# PCB_Schema.net
KiCad netlist of a schematic drawn in Altium Designer
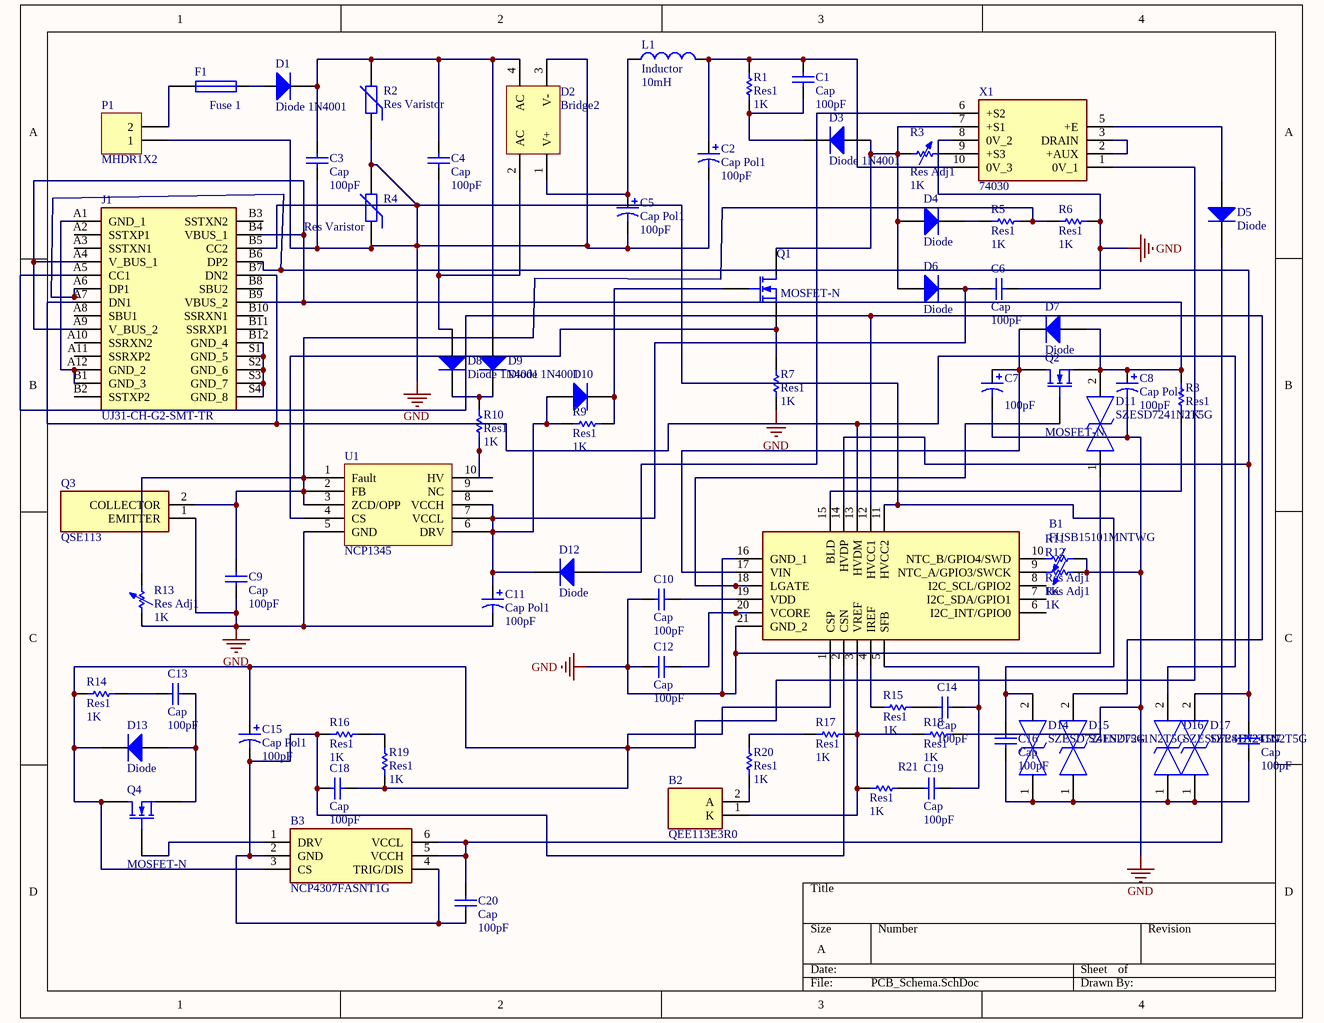
[diagram p0: PCB_Schema.SchDoc]

(export (version "E")
  (design (tool "Eeschema 10.0.6"))
  (components
    (comp (ref "B1")
      (value "FUSB15101MNTWG")
      (footprint "QFN50P400X400X100-21N")
      (description "Programmable USB Type-C and Power Delivery 3.1 Source Controller with PPS Support")
      (fields (field (name "MOUSER PART NUMBER") "863-FUSB15101MNTWG"))
      (libsource (lib "FUSB15101MNTWG") (part "FUSB15101MNTWG"))
    )
    (comp (ref "B2")
      (value "QEE113E3R0")
      (footprint "QEE113E3R0")
      (description "Infrared Emitters infrared Lt Emitting Plastic")
      (fields (field (name "MOUSER PART NUMBER") "512-QEE113E3R0"))
      (libsource (lib "QEE113E3R0") (part "QEE113E3R0"))
    )
    (comp (ref "B3")
      (value "NCP4307FASNT1G")
      (footprint "SOT95P275X110-6N")
      (description "Secondary Side Synchronous Rectification Driver with Dual Supply")
      (libsource (lib "NCP4307FASNT1G") (part "NCP4307FASNT1G"))
    )
    (comp (ref "C1")
      (value "Cap")
      (footprint "RAD-0.3")
      (description "Capacitor")
      (fields (field (name "ALTIUM_VALUE") "100pF") (field (name "PUBLISHER") "Altium Limited"))
      (libsource (lib "Miscellaneous Devices") (part "Cap"))
    )
    (comp (ref "C2")
      (value "Cap Pol1")
      (footprint "RB7.6-15")
      (description "Polarized Capacitor (Radial)")
      (fields (field (name "ALTIUM_VALUE") "100pF") (field (name "PUBLISHER") "Altium Limited"))
      (libsource (lib "Miscellaneous Devices") (part "Cap Pol1"))
    )
    (comp (ref "C3")
      (value "Cap")
      (footprint "RAD-0.3")
      (description "Capacitor")
      (fields (field (name "ALTIUM_VALUE") "100pF") (field (name "PUBLISHER") "Altium Limited"))
      (libsource (lib "Miscellaneous Devices") (part "Cap"))
    )
    (comp (ref "C4")
      (value "Cap")
      (footprint "RAD-0.3")
      (description "Capacitor")
      (fields (field (name "ALTIUM_VALUE") "100pF") (field (name "PUBLISHER") "Altium Limited"))
      (libsource (lib "Miscellaneous Devices") (part "Cap"))
    )
    (comp (ref "C5")
      (value "Cap Pol1")
      (footprint "RB7.6-15")
      (description "Polarized Capacitor (Radial)")
      (fields (field (name "ALTIUM_VALUE") "100pF") (field (name "PUBLISHER") "Altium Limited"))
      (libsource (lib "Miscellaneous Devices") (part "Cap Pol1"))
    )
    (comp (ref "C6")
      (value "Cap")
      (footprint "RAD-0.3")
      (description "Capacitor")
      (fields (field (name "ALTIUM_VALUE") "100pF") (field (name "PUBLISHER") "Altium Limited"))
      (libsource (lib "Miscellaneous Devices") (part "Cap"))
    )
    (comp (ref "C7")
      (value "100pF")
      (footprint "RB7.6-15")
      (description "Polarized Capacitor (Radial)")
      (fields (field (name "PUBLISHER") "Altium Limited"))
      (libsource (lib "Miscellaneous Devices") (part "Cap Pol1"))
    )
    (comp (ref "C8")
      (value "Cap Pol1")
      (footprint "RB7.6-15")
      (description "Polarized Capacitor (Radial)")
      (fields (field (name "ALTIUM_VALUE") "100pF") (field (name "PUBLISHER") "Altium Limited"))
      (libsource (lib "Miscellaneous Devices") (part "Cap Pol1"))
    )
    (comp (ref "C9")
      (value "Cap")
      (footprint "RAD-0.3")
      (description "Capacitor")
      (fields (field (name "ALTIUM_VALUE") "100pF") (field (name "PUBLISHER") "Altium Limited"))
      (libsource (lib "Miscellaneous Devices") (part "Cap"))
    )
    (comp (ref "C10")
      (value "Cap")
      (footprint "RAD-0.3")
      (description "Capacitor")
      (fields (field (name "ALTIUM_VALUE") "100pF") (field (name "PUBLISHER") "Altium Limited"))
      (libsource (lib "Miscellaneous Devices") (part "Cap"))
    )
    (comp (ref "C11")
      (value "Cap Pol1")
      (footprint "RB7.6-15")
      (description "Polarized Capacitor (Radial)")
      (fields (field (name "ALTIUM_VALUE") "100pF") (field (name "PUBLISHER") "Altium Limited"))
      (libsource (lib "Miscellaneous Devices") (part "Cap Pol1"))
    )
    (comp (ref "C12")
      (value "Cap")
      (footprint "RAD-0.3")
      (description "Capacitor")
      (fields (field (name "ALTIUM_VALUE") "100pF") (field (name "PUBLISHER") "Altium Limited"))
      (libsource (lib "Miscellaneous Devices") (part "Cap"))
    )
    (comp (ref "C13")
      (value "Cap")
      (footprint "RAD-0.3")
      (description "Capacitor")
      (fields (field (name "ALTIUM_VALUE") "100pF") (field (name "PUBLISHER") "Altium Limited"))
      (libsource (lib "Miscellaneous Devices") (part "Cap"))
    )
    (comp (ref "C14")
      (value "Cap")
      (footprint "RAD-0.3")
      (description "Capacitor")
      (fields (field (name "ALTIUM_VALUE") "100pF") (field (name "PUBLISHER") "Altium Limited"))
      (libsource (lib "Miscellaneous Devices") (part "Cap"))
    )
    (comp (ref "C15")
      (value "Cap Pol1")
      (footprint "RB7.6-15")
      (description "Polarized Capacitor (Radial)")
      (fields (field (name "ALTIUM_VALUE") "100pF") (field (name "PUBLISHER") "Altium Limited"))
      (libsource (lib "Miscellaneous Devices") (part "Cap Pol1"))
    )
    (comp (ref "C16")
      (value "Cap")
      (footprint "RAD-0.3")
      (description "Capacitor")
      (fields (field (name "ALTIUM_VALUE") "100pF") (field (name "PUBLISHER") "Altium Limited"))
      (libsource (lib "Miscellaneous Devices") (part "Cap"))
    )
    (comp (ref "C17")
      (value "Cap")
      (footprint "RAD-0.3")
      (description "Capacitor")
      (fields (field (name "ALTIUM_VALUE") "100pF") (field (name "PUBLISHER") "Altium Limited"))
      (libsource (lib "Miscellaneous Devices") (part "Cap"))
    )
    (comp (ref "C18")
      (value "Cap")
      (footprint "RAD-0.3")
      (description "Capacitor")
      (fields (field (name "ALTIUM_VALUE") "100pF") (field (name "PUBLISHER") "Altium Limited"))
      (libsource (lib "Miscellaneous Devices") (part "Cap"))
    )
    (comp (ref "C19")
      (value "Cap")
      (footprint "RAD-0.3")
      (description "Capacitor")
      (fields (field (name "ALTIUM_VALUE") "100pF") (field (name "PUBLISHER") "Altium Limited"))
      (libsource (lib "Miscellaneous Devices") (part "Cap"))
    )
    (comp (ref "C20")
      (value "Cap")
      (footprint "RAD-0.3")
      (description "Capacitor")
      (fields (field (name "ALTIUM_VALUE") "100pF") (field (name "PUBLISHER") "Altium Limited"))
      (libsource (lib "Miscellaneous Devices") (part "Cap"))
    )
    (comp (ref "D1")
      (value "Diode 1N4001")
      (footprint "DO-41")
      (description "1 Amp General Purpose Rectifier")
      (fields (field (name "PUBLISHER") "Altium Limited"))
      (libsource (lib "Miscellaneous Devices") (part "Diode 1N4001"))
    )
    (comp (ref "D2")
      (value "Bridge2")
      (footprint "D-46_6A")
      (description "Diode Bridge")
      (fields (field (name "PUBLISHER") "Altium Limited"))
      (libsource (lib "Miscellaneous Devices") (part "Bridge2"))
    )
    (comp (ref "D3")
      (value "Diode 1N4001")
      (footprint "DO-41")
      (description "1 Amp General Purpose Rectifier")
      (fields (field (name "PUBLISHER") "Altium Limited"))
      (libsource (lib "Miscellaneous Devices") (part "Diode 1N4001"))
    )
    (comp (ref "D4")
      (value "Diode")
      (footprint "SMC")
      (description "Default Diode")
      (fields (field (name "PUBLISHER") "Altium Limited"))
      (libsource (lib "Miscellaneous Devices") (part "Diode"))
    )
    (comp (ref "D5")
      (value "Diode")
      (footprint "SMC")
      (description "Default Diode")
      (fields (field (name "PUBLISHER") "Altium Limited"))
      (libsource (lib "Miscellaneous Devices") (part "Diode"))
    )
    (comp (ref "D6")
      (value "Diode")
      (footprint "SMC")
      (description "Default Diode")
      (fields (field (name "PUBLISHER") "Altium Limited"))
      (libsource (lib "Miscellaneous Devices") (part "Diode"))
    )
    (comp (ref "D7")
      (value "Diode")
      (footprint "SMC")
      (description "Default Diode")
      (fields (field (name "PUBLISHER") "Altium Limited"))
      (libsource (lib "Miscellaneous Devices") (part "Diode"))
    )
    (comp (ref "D8")
      (value "Diode 1N4001")
      (footprint "DO-41")
      (description "1 Amp General Purpose Rectifier")
      (fields (field (name "PUBLISHER") "Altium Limited"))
      (libsource (lib "Miscellaneous Devices") (part "Diode 1N4001"))
    )
    (comp (ref "D9")
      (value "Diode 1N4001")
      (footprint "DO-41")
      (description "1 Amp General Purpose Rectifier")
      (fields (field (name "PUBLISHER") "Altium Limited"))
      (libsource (lib "Miscellaneous Devices") (part "Diode 1N4001"))
    )
    (comp (ref "D10")
      (value "~")
      (footprint "SMC")
      (description "Default Diode")
      (fields (field (name "PUBLISHER") "Altium Limited"))
      (libsource (lib "Miscellaneous Devices") (part "Diode"))
    )
    (comp (ref "D11")
      (value "SZESD7241N2T5G")
      (footprint "SZESD7462N2T5G")
      (description "ESD Suppressors / TVS Diodes SZ 24V VRWM ESD PROTECTION")
      (fields (field (name "MOUSER PART NUMBER") "863-SZESD7241N2T5G"))
      (libsource (lib "SZESD7241N2T5G") (part "SZESD7241N2T5G"))
    )
    (comp (ref "D12")
      (value "Diode")
      (footprint "SMC")
      (description "Default Diode")
      (fields (field (name "PUBLISHER") "Altium Limited"))
      (libsource (lib "Miscellaneous Devices") (part "Diode"))
    )
    (comp (ref "D13")
      (value "Diode")
      (footprint "SMC")
      (description "Default Diode")
      (fields (field (name "PUBLISHER") "Altium Limited"))
      (libsource (lib "Miscellaneous Devices") (part "Diode"))
    )
    (comp (ref "D14")
      (value "SZESD7241N2T5G")
      (footprint "SZESD7462N2T5G")
      (description "ESD Suppressors / TVS Diodes SZ 24V VRWM ESD PROTECTION")
      (fields (field (name "MOUSER PART NUMBER") "863-SZESD7241N2T5G"))
      (libsource (lib "SZESD7241N2T5G") (part "SZESD7241N2T5G"))
    )
    (comp (ref "D15")
      (value "SZESD7241N2T5G")
      (footprint "SZESD7462N2T5G")
      (description "ESD Suppressors / TVS Diodes SZ 24V VRWM ESD PROTECTION")
      (fields (field (name "MOUSER PART NUMBER") "863-SZESD7241N2T5G"))
      (libsource (lib "SZESD7241N2T5G") (part "SZESD7241N2T5G"))
    )
    (comp (ref "D16")
      (value "SZESD7241N2T5G")
      (footprint "SZESD7462N2T5G")
      (description "ESD Suppressors / TVS Diodes SZ 24V VRWM ESD PROTECTION")
      (fields (field (name "MOUSER PART NUMBER") "863-SZESD7241N2T5G"))
      (libsource (lib "SZESD7241N2T5G") (part "SZESD7241N2T5G"))
    )
    (comp (ref "D17")
      (value "SZESD7241N2T5G")
      (footprint "SZESD7462N2T5G")
      (description "ESD Suppressors / TVS Diodes SZ 24V VRWM ESD PROTECTION")
      (fields (field (name "MOUSER PART NUMBER") "863-SZESD7241N2T5G"))
      (libsource (lib "SZESD7241N2T5G") (part "SZESD7241N2T5G"))
    )
    (comp (ref "F1")
      (value "Fuse 1")
      (footprint "PIN-W2/E2.8")
      (description "Fuse")
      (fields (field (name "PUBLISHER") "Altium Limited"))
      (libsource (lib "Miscellaneous Devices") (part "Fuse 1"))
    )
    (comp (ref "J1")
      (value "UJ31-CH-G2-SMT-TR")
      (footprint "UJ31CHG2SMTTR")
      (description "USB Connectors USB jack 3.1 C type 24pin Horz SMT")
      (fields (field (name "MOUSER PART NUMBER") "490-UJ31-CH-G2SMT-TR"))
      (libsource (lib "UJ31-CH-G2-SMT-TR") (part "UJ31-CH-G2-SMT-TR"))
    )
    (comp (ref "L1")
      (value "Inductor")
      (footprint "0402-A")
      (fields (field (name "ALTIUM_VALUE") "10mH") (field (name "PUBLISHER") "Altium Limited"))
      (libsource (lib "Miscellaneous Devices") (part "Inductor"))
    )
    (comp (ref "P1")
      (value "MHDR1X2")
      (footprint "MHDR1X2")
      (description "Header, 2-Pin")
      (fields (field (name "PUBLISHER") "Altium Limited"))
      (libsource (lib "Miscellaneous Connectors") (part "MHDR1X2"))
    )
    (comp (ref "Q1")
      (value "MOSFET-N")
      (footprint "E3")
      (description "N-Channel MOSFET")
      (fields (field (name "PUBLISHER") "Altium Limited"))
      (libsource (lib "Miscellaneous Devices") (part "MOSFET-N"))
    )
    (comp (ref "Q2")
      (value "MOSFET-N")
      (footprint "E3")
      (description "N-Channel MOSFET")
      (fields (field (name "PUBLISHER") "Altium Limited"))
      (libsource (lib "Miscellaneous Devices") (part "MOSFET-N"))
    )
    (comp (ref "Q3")
      (value "QSE113")
      (footprint "TO254P304X444X533-2P")
      (fields (field (name "MOUSER PART NUMBER") "512-QSE113"))
      (libsource (lib "QSE113") (part "QSE113"))
    )
    (comp (ref "Q4")
      (value "MOSFET-N")
      (footprint "E3")
      (description "N-Channel MOSFET")
      (fields (field (name "PUBLISHER") "Altium Limited"))
      (libsource (lib "Miscellaneous Devices") (part "MOSFET-N"))
    )
    (comp (ref "R1")
      (value "Res1")
      (footprint "AXIAL-0.3")
      (description "Resistor")
      (fields (field (name "ALTIUM_VALUE") "1K") (field (name "PUBLISHER") "Altium Limited"))
      (libsource (lib "Miscellaneous Devices") (part "Res1"))
    )
    (comp (ref "R2")
      (value "Res Varistor")
      (footprint "6-0805_N")
      (description "Varistor (Voltage-Sensitive Resistor)")
      (fields (field (name "PUBLISHER") "Altium Limited"))
      (libsource (lib "Miscellaneous Devices") (part "Res Varistor"))
    )
    (comp (ref "R3")
      (value "Res Adj1")
      (footprint "AXIAL-0.7")
      (description "Variable Resistor")
      (fields (field (name "ALTIUM_VALUE") "1K") (field (name "PUBLISHER") "Altium Limited"))
      (libsource (lib "Miscellaneous Devices") (part "Res Adj1"))
    )
    (comp (ref "R4")
      (value "Res Varistor")
      (footprint "6-0805_N")
      (description "Varistor (Voltage-Sensitive Resistor)")
      (fields (field (name "PUBLISHER") "Altium Limited"))
      (libsource (lib "Miscellaneous Devices") (part "Res Varistor"))
    )
    (comp (ref "R5")
      (value "Res1")
      (footprint "AXIAL-0.3")
      (description "Resistor")
      (fields (field (name "ALTIUM_VALUE") "1K") (field (name "PUBLISHER") "Altium Limited"))
      (libsource (lib "Miscellaneous Devices") (part "Res1"))
    )
    (comp (ref "R6")
      (value "Res1")
      (footprint "AXIAL-0.3")
      (description "Resistor")
      (fields (field (name "ALTIUM_VALUE") "1K") (field (name "PUBLISHER") "Altium Limited"))
      (libsource (lib "Miscellaneous Devices") (part "Res1"))
    )
    (comp (ref "R7")
      (value "Res1")
      (footprint "AXIAL-0.3")
      (description "Resistor")
      (fields (field (name "ALTIUM_VALUE") "1K") (field (name "PUBLISHER") "Altium Limited"))
      (libsource (lib "Miscellaneous Devices") (part "Res1"))
    )
    (comp (ref "R8")
      (value "Res1")
      (footprint "AXIAL-0.3")
      (description "Resistor")
      (fields (field (name "ALTIUM_VALUE") "1K") (field (name "PUBLISHER") "Altium Limited"))
      (libsource (lib "Miscellaneous Devices") (part "Res1"))
    )
    (comp (ref "R9")
      (value "Res1")
      (footprint "AXIAL-0.3")
      (description "Resistor")
      (fields (field (name "ALTIUM_VALUE") "1K") (field (name "PUBLISHER") "Altium Limited"))
      (libsource (lib "Miscellaneous Devices") (part "Res1"))
    )
    (comp (ref "R10")
      (value "Res1")
      (footprint "AXIAL-0.3")
      (description "Resistor")
      (fields (field (name "ALTIUM_VALUE") "1K") (field (name "PUBLISHER") "Altium Limited"))
      (libsource (lib "Miscellaneous Devices") (part "Res1"))
    )
    (comp (ref "R11")
      (value "Res Adj1")
      (footprint "AXIAL-0.7")
      (description "Variable Resistor")
      (fields (field (name "ALTIUM_VALUE") "1K") (field (name "PUBLISHER") "Altium Limited"))
      (libsource (lib "Miscellaneous Devices") (part "Res Adj1"))
    )
    (comp (ref "R12")
      (value "Res Adj1")
      (footprint "AXIAL-0.7")
      (description "Variable Resistor")
      (fields (field (name "ALTIUM_VALUE") "1K") (field (name "PUBLISHER") "Altium Limited"))
      (libsource (lib "Miscellaneous Devices") (part "Res Adj1"))
    )
    (comp (ref "R13")
      (value "Res Adj1")
      (footprint "AXIAL-0.7")
      (description "Variable Resistor")
      (fields (field (name "ALTIUM_VALUE") "1K") (field (name "PUBLISHER") "Altium Limited"))
      (libsource (lib "Miscellaneous Devices") (part "Res Adj1"))
    )
    (comp (ref "R14")
      (value "Res1")
      (footprint "AXIAL-0.3")
      (description "Resistor")
      (fields (field (name "ALTIUM_VALUE") "1K") (field (name "PUBLISHER") "Altium Limited"))
      (libsource (lib "Miscellaneous Devices") (part "Res1"))
    )
    (comp (ref "R15")
      (value "Res1")
      (footprint "AXIAL-0.3")
      (description "Resistor")
      (fields (field (name "ALTIUM_VALUE") "1K") (field (name "PUBLISHER") "Altium Limited"))
      (libsource (lib "Miscellaneous Devices") (part "Res1"))
    )
    (comp (ref "R16")
      (value "Res1")
      (footprint "AXIAL-0.3")
      (description "Resistor")
      (fields (field (name "ALTIUM_VALUE") "1K") (field (name "PUBLISHER") "Altium Limited"))
      (libsource (lib "Miscellaneous Devices") (part "Res1"))
    )
    (comp (ref "R17")
      (value "Res1")
      (footprint "AXIAL-0.3")
      (description "Resistor")
      (fields (field (name "ALTIUM_VALUE") "1K") (field (name "PUBLISHER") "Altium Limited"))
      (libsource (lib "Miscellaneous Devices") (part "Res1"))
    )
    (comp (ref "R18")
      (value "Res1")
      (footprint "AXIAL-0.3")
      (description "Resistor")
      (fields (field (name "ALTIUM_VALUE") "1K") (field (name "PUBLISHER") "Altium Limited"))
      (libsource (lib "Miscellaneous Devices") (part "Res1"))
    )
    (comp (ref "R19")
      (value "Res1")
      (footprint "AXIAL-0.3")
      (description "Resistor")
      (fields (field (name "ALTIUM_VALUE") "1K") (field (name "PUBLISHER") "Altium Limited"))
      (libsource (lib "Miscellaneous Devices") (part "Res1"))
    )
    (comp (ref "R20")
      (value "Res1")
      (footprint "AXIAL-0.3")
      (description "Resistor")
      (fields (field (name "ALTIUM_VALUE") "1K") (field (name "PUBLISHER") "Altium Limited"))
      (libsource (lib "Miscellaneous Devices") (part "Res1"))
    )
    (comp (ref "R21")
      (value "Res1")
      (footprint "AXIAL-0.3")
      (description "Resistor")
      (fields (field (name "ALTIUM_VALUE") "1K") (field (name "PUBLISHER") "Altium Limited"))
      (libsource (lib "Miscellaneous Devices") (part "Res1"))
    )
    (comp (ref "U1")
      (value "NCP1345")
      (footprint "SOP100P600X265-10N")
      (libsource (lib "ncp1345") (part "NCP1345"))
    )
    (comp (ref "X1") (value "74030") (footprint "74030") (libsource (lib "74030") (part "74030")))
  )
  (nets
    (net (code "1") (name "GND") (class "Default")
      (node (ref "B1") (pin "11") (pinfunction "HVCC2_11") (pintype "passive"))
      (node (ref "B1") (pin "16") (pinfunction "GND_1_16") (pintype "passive"))
      (node (ref "B1") (pin "21") (pinfunction "GND_2_21") (pintype "passive"))
      (node (ref "C10") (pin "1") (pinfunction "1_1") (pintype "passive"))
      (node (ref "C11") (pin "2") (pinfunction "2_2") (pintype "passive"))
      (node (ref "C12") (pin "1") (pinfunction "1_1") (pintype "passive"))
      (node (ref "C16") (pin "2") (pinfunction "2_2") (pintype "passive"))
      (node (ref "C2") (pin "2") (pinfunction "2_2") (pintype "passive"))
      (node (ref "C3") (pin "1") (pinfunction "1_1") (pintype "passive"))
      (node (ref "C5") (pin "2") (pinfunction "2_2") (pintype "passive"))
      (node (ref "C6") (pin "1") (pinfunction "1_1") (pintype "passive"))
      (node (ref "C7") (pin "2") (pinfunction "2_2") (pintype "passive"))
      (node (ref "C8") (pin "2") (pinfunction "2_2") (pintype "passive"))
      (node (ref "C9") (pin "1") (pinfunction "1_1") (pintype "passive"))
      (node (ref "D11") (pin "1") (pinfunction "1_1") (pintype "passive"))
      (node (ref "D14") (pin "2") (pinfunction "2_2") (pintype "passive"))
      (node (ref "D2") (pin "3") (pinfunction "V-_3") (pintype "passive"))
      (node (ref "J1") (pin "B5") (pinfunction "CC2_B5") (pintype "passive"))
      (node (ref "P1") (pin "1") (pinfunction "1_1") (pintype "passive"))
      (node (ref "Q3") (pin "1") (pinfunction "EMITTER_1") (pintype "passive"))
      (node (ref "R11") (pin "1") (pinfunction "1_1") (pintype "passive"))
      (node (ref "R12") (pin "1") (pinfunction "1_1") (pintype "passive"))
      (node (ref "R13") (pin "1") (pinfunction "1_1") (pintype "passive"))
      (node (ref "R18") (pin "1") (pinfunction "1_1") (pintype "passive"))
      (node (ref "R2") (pin "1") (pinfunction "1_1") (pintype "passive"))
      (node (ref "R4") (pin "1") (pinfunction "1_1") (pintype "passive"))
      (node (ref "R4") (pin "2") (pinfunction "2_2") (pintype "passive"))
      (node (ref "R6") (pin "1") (pinfunction "1_1") (pintype "passive"))
      (node (ref "R7") (pin "1") (pinfunction "1_1") (pintype "passive"))
      (node (ref "U1") (pin "5") (pinfunction "GND_5") (pintype "passive"))
      (node (ref "X1") (pin "8") (pinfunction "0V_2_8") (pintype "passive"))
    )
    (net (code "2") (name "Net-(B1-BLD)") (class "Default")
      (node (ref "B1") (pin "15") (pinfunction "BLD_15") (pintype "passive"))
      (node (ref "R8") (pin "1") (pinfunction "1_1") (pintype "passive"))
    )
    (net (code "3") (name "Net-(B1-CSN)") (class "Default")
      (node (ref "B1") (pin "2") (pinfunction "CSN_2") (pintype "passive"))
      (node (ref "B3") (pin "2") (pinfunction "GND_2") (pintype "passive"))
      (node (ref "B3") (pin "4") (pinfunction "TRIG/DIS_4") (pintype "passive"))
      (node (ref "C15") (pin "2") (pinfunction "2_2") (pintype "passive"))
      (node (ref "C18") (pin "1") (pinfunction "1_1") (pintype "passive"))
      (node (ref "C20") (pin "2") (pinfunction "2_2") (pintype "passive"))
      (node (ref "R16") (pin "1") (pinfunction "1_1") (pintype "passive"))
    )
    (net (code "4") (name "Net-(B1-CSP)") (class "Default")
      (node (ref "B1") (pin "1") (pinfunction "CSP_1") (pintype "passive"))
      (node (ref "B3") (pin "3") (pinfunction "CS_3") (pintype "passive"))
      (node (ref "C15") (pin "1") (pinfunction "1_1") (pintype "passive"))
      (node (ref "C18") (pin "2") (pinfunction "2_2") (pintype "passive"))
      (node (ref "D13") (pin "2") (pinfunction "K_2") (pintype "passive"))
      (node (ref "Q4") (pin "1") (pinfunction "D_1") (pintype "passive"))
      (node (ref "R14") (pin "1") (pinfunction "1_1") (pintype "passive"))
      (node (ref "R19") (pin "1") (pinfunction "1_1") (pintype "passive"))
      (node (ref "X1") (pin "1") (pinfunction "0V_1_1") (pintype "passive"))
    )
    (net (code "5") (name "Net-(B1-HVCC1)") (class "Default")
      (node (ref "B1") (pin "12") (pinfunction "HVCC1_12") (pintype "passive"))
      (node (ref "D15") (pin "2") (pinfunction "2_2") (pintype "passive"))
      (node (ref "J1") (pin "A5") (pinfunction "CC1_A5") (pintype "passive"))
    )
    (net (code "6") (name "Net-(B1-HVDM)") (class "Default")
      (node (ref "B1") (pin "13") (pinfunction "HVDM_13") (pintype "passive"))
      (node (ref "D16") (pin "2") (pinfunction "2_2") (pintype "passive"))
      (node (ref "J1") (pin "A7") (pinfunction "DN1_A7") (pintype "passive"))
      (node (ref "J1") (pin "B7") (pinfunction "DN2_B7") (pintype "passive"))
    )
    (net (code "7") (name "Net-(B1-HVDP)") (class "Default")
      (node (ref "B1") (pin "14") (pinfunction "HVDP_14") (pintype "passive"))
      (node (ref "C17") (pin "2") (pinfunction "2_2") (pintype "passive"))
      (node (ref "D17") (pin "2") (pinfunction "2_2") (pintype "passive"))
      (node (ref "J1") (pin "A6") (pinfunction "DP1_A6") (pintype "passive"))
      (node (ref "J1") (pin "B6") (pinfunction "DP2_B6") (pintype "passive"))
    )
    (net (code "8") (name "Net-(B1-IREF)") (class "Default")
      (node (ref "B1") (pin "4") (pinfunction "IREF_4") (pintype "passive"))
      (node (ref "R15") (pin "1") (pinfunction "1_1") (pintype "passive"))
    )
    (net (code "9") (name "Net-(B1-LGATE)") (class "Default")
      (node (ref "B1") (pin "18") (pinfunction "LGATE_18") (pintype "passive"))
      (node (ref "Q2") (pin "2") (pinfunction "G_2") (pintype "passive"))
    )
    (net (code "10") (name "Net-(B1-SFB)") (class "Default")
      (node (ref "B1") (pin "5") (pinfunction "SFB_5") (pintype "passive"))
      (node (ref "C14") (pin "2") (pinfunction "2_2") (pintype "passive"))
      (node (ref "C19") (pin "2") (pinfunction "2_2") (pintype "passive"))
    )
    (net (code "11") (name "Net-(B1-VCORE)") (class "Default")
      (node (ref "B1") (pin "20") (pinfunction "VCORE_20") (pintype "passive"))
      (node (ref "C12") (pin "2") (pinfunction "2_2") (pintype "passive"))
    )
    (net (code "12") (name "Net-(B1-VDD)") (class "Default")
      (node (ref "B1") (pin "19") (pinfunction "VDD_19") (pintype "passive"))
      (node (ref "C10") (pin "2") (pinfunction "2_2") (pintype "passive"))
    )
    (net (code "13") (name "Net-(B1-VIN)") (class "Default")
      (node (ref "B1") (pin "17") (pinfunction "VIN_17") (pintype "passive"))
      (node (ref "C7") (pin "1") (pinfunction "1_1") (pintype "passive"))
      (node (ref "D7") (pin "2") (pinfunction "K_2") (pintype "passive"))
      (node (ref "Q2") (pin "1") (pinfunction "D_1") (pintype "passive"))
    )
    (net (code "14") (name "Net-(B1-VREF)") (class "Default")
      (node (ref "B1") (pin "3") (pinfunction "VREF_3") (pintype "passive"))
      (node (ref "B2") (pin "1") (pinfunction "K_1") (pintype "passive"))
      (node (ref "R17") (pin "1") (pinfunction "1_1") (pintype "passive"))
      (node (ref "R18") (pin "2") (pinfunction "2_2") (pintype "passive"))
      (node (ref "R21") (pin "1") (pinfunction "1_1") (pintype "passive"))
    )
    (net (code "15") (name "Net-(B2-A)") (class "Default")
      (node (ref "B2") (pin "2") (pinfunction "A_2") (pintype "passive"))
      (node (ref "R20") (pin "1") (pinfunction "1_1") (pintype "passive"))
    )
    (net (code "16") (name "Net-(B3-DRV)") (class "Default")
      (node (ref "B3") (pin "1") (pinfunction "DRV_1") (pintype "passive"))
      (node (ref "Q4") (pin "2") (pinfunction "G_2") (pintype "passive"))
    )
    (net (code "17") (name "Net-(B3-VCCH)") (class "Default")
      (node (ref "B3") (pin "5") (pinfunction "VCCH_5") (pintype "passive"))
      (node (ref "B3") (pin "6") (pinfunction "VCCL_6") (pintype "passive"))
      (node (ref "C20") (pin "1") (pinfunction "1_1") (pintype "passive"))
      (node (ref "D5") (pin "2") (pinfunction "K_2") (pintype "passive"))
    )
    (net (code "18") (name "Net-(C13-Pad1)") (class "Default")
      (node (ref "C13") (pin "1") (pinfunction "1_1") (pintype "passive"))
      (node (ref "R14") (pin "2") (pinfunction "2_2") (pintype "passive"))
    )
    (net (code "19") (name "Net-(C14-Pad1)") (class "Default")
      (node (ref "C14") (pin "1") (pinfunction "1_1") (pintype "passive"))
      (node (ref "R15") (pin "2") (pinfunction "2_2") (pintype "passive"))
    )
    (net (code "20") (name "Net-(C16-Pad1)") (class "Default")
      (node (ref "C16") (pin "1") (pinfunction "1_1") (pintype "passive"))
      (node (ref "C17") (pin "1") (pinfunction "1_1") (pintype "passive"))
      (node (ref "D14") (pin "1") (pinfunction "1_1") (pintype "passive"))
      (node (ref "D15") (pin "1") (pinfunction "1_1") (pintype "passive"))
      (node (ref "D16") (pin "1") (pinfunction "1_1") (pintype "passive"))
      (node (ref "D17") (pin "1") (pinfunction "1_1") (pintype "passive"))
    )
    (net (code "21") (name "Net-(C19-Pad1)") (class "Default")
      (node (ref "C19") (pin "1") (pinfunction "1_1") (pintype "passive"))
      (node (ref "R21") (pin "2") (pinfunction "2_2") (pintype "passive"))
    )
    (net (code "22") (name "Net-(D1-A)") (class "Default")
      (node (ref "D1") (pin "1") (pinfunction "A_1") (pintype "passive"))
      (node (ref "F1") (pin "2") (pinfunction "2_2") (pintype "passive"))
    )
    (net (code "23") (name "Net-(D1-K)") (class "Default")
      (node (ref "C3") (pin "2") (pinfunction "2_2") (pintype "passive"))
      (node (ref "C4") (pin "2") (pinfunction "2_2") (pintype "passive"))
      (node (ref "D1") (pin "2") (pinfunction "K_2") (pintype "passive"))
      (node (ref "D2") (pin "4") (pinfunction "AC_4") (pintype "passive"))
      (node (ref "D9") (pin "1") (pinfunction "A_1") (pintype "passive"))
      (node (ref "R2") (pin "2") (pinfunction "2_2") (pintype "passive"))
    )
    (net (code "24") (name "Net-(D2-V+)") (class "Default")
      (node (ref "C5") (pin "1") (pinfunction "1_1") (pintype "passive"))
      (node (ref "D2") (pin "1") (pinfunction "V+_1") (pintype "passive"))
      (node (ref "L1") (pin "1") (pinfunction "1_1") (pintype "passive"))
    )
    (net (code "25") (name "Net-(D3-A)") (class "Default")
      (node (ref "D3") (pin "1") (pinfunction "A_1") (pintype "passive"))
      (node (ref "D4") (pin "1") (pinfunction "A_1") (pintype "passive"))
      (node (ref "D6") (pin "1") (pinfunction "A_1") (pintype "passive"))
      (node (ref "Q1") (pin "1") (pinfunction "D_1") (pintype "passive"))
      (node (ref "R3") (pin "1") (pinfunction "1_1") (pintype "passive"))
      (node (ref "X1") (pin "7") (pinfunction "+S1_7") (pintype "passive"))
    )
    (net (code "26") (name "Net-(D3-K)") (class "Default")
      (node (ref "C1") (pin "1") (pinfunction "1_1") (pintype "passive"))
      (node (ref "D3") (pin "2") (pinfunction "K_2") (pintype "passive"))
      (node (ref "R1") (pin "1") (pinfunction "1_1") (pintype "passive"))
    )
    (net (code "27") (name "Net-(D4-K)") (class "Default")
      (node (ref "D4") (pin "2") (pinfunction "K_2") (pintype "passive"))
      (node (ref "R5") (pin "2") (pinfunction "2_2") (pintype "passive"))
    )
    (net (code "28") (name "Net-(D5-A)") (class "Default")
      (node (ref "D5") (pin "1") (pinfunction "A_1") (pintype "passive"))
      (node (ref "X1") (pin "5") (pinfunction "+E_5") (pintype "passive"))
    )
    (net (code "29") (name "Net-(D7-A)") (class "Default")
      (node (ref "C8") (pin "1") (pinfunction "1_1") (pintype "passive"))
      (node (ref "D11") (pin "2") (pinfunction "2_2") (pintype "passive"))
      (node (ref "D7") (pin "1") (pinfunction "A_1") (pintype "passive"))
      (node (ref "J1") (pin "A4") (pinfunction "V_BUS_1_A4") (pintype "passive"))
      (node (ref "J1") (pin "A9") (pinfunction "V_BUS_2_A9") (pintype "passive"))
      (node (ref "J1") (pin "B4") (pinfunction "VBUS_1_B4") (pintype "passive"))
      (node (ref "J1") (pin "B9") (pinfunction "VBUS_2_B9") (pintype "passive"))
      (node (ref "Q2") (pin "3") (pinfunction "S_3") (pintype "passive"))
      (node (ref "R8") (pin "2") (pinfunction "2_2") (pintype "passive"))
    )
    (net (code "30") (name "Net-(D8-A)") (class "Default")
      (node (ref "C4") (pin "1") (pinfunction "1_1") (pintype "passive"))
      (node (ref "D2") (pin "2") (pinfunction "AC_2") (pintype "passive"))
      (node (ref "D8") (pin "1") (pinfunction "A_1") (pintype "passive"))
    )
    (net (code "31") (name "Net-(D8-K)") (class "Default")
      (node (ref "D8") (pin "2") (pinfunction "K_2") (pintype "passive"))
      (node (ref "D9") (pin "2") (pinfunction "K_2") (pintype "passive"))
      (node (ref "R10") (pin "2") (pinfunction "2_2") (pintype "passive"))
    )
    (net (code "32") (name "Net-(D10-A)") (class "Default")
      (node (ref "C11") (pin "1") (pinfunction "1_1") (pintype "passive"))
      (node (ref "C6") (pin "2") (pinfunction "2_2") (pintype "passive"))
      (node (ref "D10") (pin "1") (pinfunction "A_1") (pintype "passive"))
      (node (ref "D12") (pin "2") (pinfunction "K_2") (pintype "passive"))
      (node (ref "D6") (pin "2") (pinfunction "K_2") (pintype "passive"))
      (node (ref "R9") (pin "1") (pinfunction "1_1") (pintype "passive"))
      (node (ref "U1") (pin "6") (pinfunction "DRV_6") (pintype "passive"))
      (node (ref "U1") (pin "7") (pinfunction "VCCL_7") (pintype "passive"))
      (node (ref "U1") (pin "8") (pinfunction "VCCH_8") (pintype "passive"))
    )
    (net (code "33") (name "Net-(D10-K)") (class "Default")
      (node (ref "D10") (pin "2") (pinfunction "K_2") (pintype "passive"))
      (node (ref "Q1") (pin "2") (pinfunction "G_2") (pintype "passive"))
      (node (ref "R9") (pin "2") (pinfunction "2_2") (pintype "passive"))
    )
    (net (code "34") (name "Net-(D12-A)") (class "Default")
      (node (ref "D12") (pin "1") (pinfunction "A_1") (pintype "passive"))
      (node (ref "X1") (pin "6") (pinfunction "+S2_6") (pintype "passive"))
    )
    (net (code "35") (name "Net-(D13-A)") (class "Default")
      (node (ref "C13") (pin "2") (pinfunction "2_2") (pintype "passive"))
      (node (ref "D13") (pin "1") (pinfunction "A_1") (pintype "passive"))
      (node (ref "Q4") (pin "3") (pinfunction "S_3") (pintype "passive"))
    )
    (net (code "36") (name "Net-(F1-Pad1)") (class "Default")
      (node (ref "F1") (pin "1") (pinfunction "1_1") (pintype "passive"))
      (node (ref "P1") (pin "2") (pinfunction "2_2") (pintype "passive"))
    )
    (net (code "37") (name "Net-(J1-GND_1)") (class "Default")
      (node (ref "J1") (pin "A1") (pinfunction "GND_1_A1") (pintype "passive"))
      (node (ref "J1") (pin "A12") (pinfunction "GND_2_A12") (pintype "passive"))
      (node (ref "J1") (pin "B1") (pinfunction "GND_3_B1") (pintype "passive"))
    )
    (net (code "38") (name "Net-(J1-GND_4)") (class "Default")
      (node (ref "J1") (pin "B12") (pinfunction "GND_4_B12") (pintype "passive"))
      (node (ref "J1") (pin "S1") (pinfunction "GND_5_S1") (pintype "passive"))
      (node (ref "J1") (pin "S2") (pinfunction "GND_6_S2") (pintype "passive"))
      (node (ref "J1") (pin "S3") (pinfunction "GND_7_S3") (pintype "passive"))
      (node (ref "J1") (pin "S4") (pinfunction "GND_8_S4") (pintype "passive"))
    )
    (net (code "39") (name "Net-(Q1-S)") (class "Default")
      (node (ref "Q1") (pin "3") (pinfunction "S_3") (pintype "passive"))
      (node (ref "R7") (pin "2") (pinfunction "2_2") (pintype "passive"))
      (node (ref "U1") (pin "4") (pinfunction "CS_4") (pintype "passive"))
    )
    (net (code "40") (name "Net-(Q3-COLLECTOR)") (class "Default")
      (node (ref "C9") (pin "2") (pinfunction "2_2") (pintype "passive"))
      (node (ref "Q3") (pin "2") (pinfunction "COLLECTOR_2") (pintype "passive"))
      (node (ref "R13") (pin "2") (pinfunction "2_2") (pintype "passive"))
      (node (ref "R5") (pin "1") (pinfunction "1_1") (pintype "passive"))
      (node (ref "R6") (pin "2") (pinfunction "2_2") (pintype "passive"))
      (node (ref "U1") (pin "1") (pinfunction "Fault_1") (pintype "passive"))
      (node (ref "U1") (pin "2") (pinfunction "FB_2") (pintype "passive"))
      (node (ref "U1") (pin "3") (pinfunction "ZCD/OPP_3") (pintype "passive"))
    )
    (net (code "41") (name "Net-(R16-Pad2)") (class "Default")
      (node (ref "R16") (pin "2") (pinfunction "2_2") (pintype "passive"))
      (node (ref "R19") (pin "2") (pinfunction "2_2") (pintype "passive"))
    )
    (net (code "42") (name "Net-(R17-Pad2)") (class "Default")
      (node (ref "R17") (pin "2") (pinfunction "2_2") (pintype "passive"))
      (node (ref "R20") (pin "2") (pinfunction "2_2") (pintype "passive"))
    )
    (net (code "43") (name "Net-(U1-HV)") (class "Default")
      (node (ref "R10") (pin "1") (pinfunction "1_1") (pintype "passive"))
      (node (ref "U1") (pin "10") (pinfunction "HV_10") (pintype "passive"))
    )
    (net (code "44") (name "Net-(X1-+AUX)") (class "Default")
      (node (ref "X1") (pin "2") (pinfunction "+AUX_2") (pintype "passive"))
      (node (ref "X1") (pin "3") (pinfunction "DRAIN_3") (pintype "passive"))
    )
    (net (code "45") (name "Net-(X1-+S3)") (class "Default")
      (node (ref "R3") (pin "2") (pinfunction "2_2") (pintype "passive"))
      (node (ref "X1") (pin "9") (pinfunction "+S3_9") (pintype "passive"))
    )
    (net (code "46") (name "Net-(X1-0V_3)") (class "Default")
      (node (ref "C1") (pin "2") (pinfunction "2_2") (pintype "passive"))
      (node (ref "C2") (pin "1") (pinfunction "1_1") (pintype "passive"))
      (node (ref "L1") (pin "2") (pinfunction "2_2") (pintype "passive"))
      (node (ref "R1") (pin "2") (pinfunction "2_2") (pintype "passive"))
      (node (ref "X1") (pin "10") (pinfunction "0V_3_10") (pintype "passive"))
    )
    (net (code "47") (name "unconnected-(B1-I2C_INT{slash}GPIO0-Pad6)") (class "Default")
      (node (ref "B1") (pin "6") (pinfunction "I2C_INT/GPIO0_6") (pintype "passive"))
    )
    (net (code "48") (name "unconnected-(B1-I2C_SCL{slash}GPIO2-Pad8)") (class "Default")
      (node (ref "B1") (pin "8") (pinfunction "I2C_SCL/GPIO2_8") (pintype "passive"))
    )
    (net (code "49") (name "unconnected-(B1-I2C_SDA{slash}GPIO1-Pad7)") (class "Default")
      (node (ref "B1") (pin "7") (pinfunction "I2C_SDA/GPIO1_7") (pintype "passive"))
    )
    (net (code "50") (name "unconnected-(B1-NTC_A{slash}GPIO3{slash}SWCK-Pad9)") (class "Default")
      (node (ref "B1") (pin "9") (pinfunction "NTC_A/GPIO3/SWCK_9") (pintype "passive"))
    )
    (net (code "51") (name "unconnected-(B1-NTC_B{slash}GPIO4{slash}SWD-Pad10)") (class "Default")
      (node (ref "B1") (pin "10") (pinfunction "NTC_B/GPIO4/SWD_10") (pintype "passive"))
    )
    (net (code "52") (name "unconnected-(J1-SBU1-PadA8)") (class "Default")
      (node (ref "J1") (pin "A8") (pinfunction "SBU1_A8") (pintype "passive"))
    )
    (net (code "53") (name "unconnected-(J1-SBU2-PadB8)") (class "Default")
      (node (ref "J1") (pin "B8") (pinfunction "SBU2_B8") (pintype "passive"))
    )
    (net (code "54") (name "unconnected-(J1-SSRXN1-PadB10)") (class "Default")
      (node (ref "J1") (pin "B10") (pinfunction "SSRXN1_B10") (pintype "passive"))
    )
    (net (code "55") (name "unconnected-(J1-SSRXN2-PadA10)") (class "Default")
      (node (ref "J1") (pin "A10") (pinfunction "SSRXN2_A10") (pintype "passive"))
    )
    (net (code "56") (name "unconnected-(J1-SSRXP1-PadB11)") (class "Default")
      (node (ref "J1") (pin "B11") (pinfunction "SSRXP1_B11") (pintype "passive"))
    )
    (net (code "57") (name "unconnected-(J1-SSRXP2-PadA11)") (class "Default")
      (node (ref "J1") (pin "A11") (pinfunction "SSRXP2_A11") (pintype "passive"))
    )
    (net (code "58") (name "unconnected-(J1-SSTXN1-PadA3)") (class "Default")
      (node (ref "J1") (pin "A3") (pinfunction "SSTXN1_A3") (pintype "passive"))
    )
    (net (code "59") (name "unconnected-(J1-SSTXN2-PadB3)") (class "Default")
      (node (ref "J1") (pin "B3") (pinfunction "SSTXN2_B3") (pintype "passive"))
    )
    (net (code "60") (name "unconnected-(J1-SSTXP1-PadA2)") (class "Default")
      (node (ref "J1") (pin "A2") (pinfunction "SSTXP1_A2") (pintype "passive"))
    )
    (net (code "61") (name "unconnected-(J1-SSTXP2-PadB2)") (class "Default")
      (node (ref "J1") (pin "B2") (pinfunction "SSTXP2_B2") (pintype "passive"))
    )
    (net (code "62") (name "unconnected-(R11-Pad2)") (class "Default")
      (node (ref "R11") (pin "2") (pinfunction "2_2") (pintype "passive"))
    )
    (net (code "63") (name "unconnected-(R12-Pad2)") (class "Default")
      (node (ref "R12") (pin "2") (pinfunction "2_2") (pintype "passive"))
    )
    (net (code "64") (name "unconnected-(U1-NC-Pad9)") (class "Default")
      (node (ref "U1") (pin "9") (pinfunction "NC_9") (pintype "passive"))
    )
  )
)
